# GateDriver.net
KiCad netlist of a schematic drawn in Altium Designer
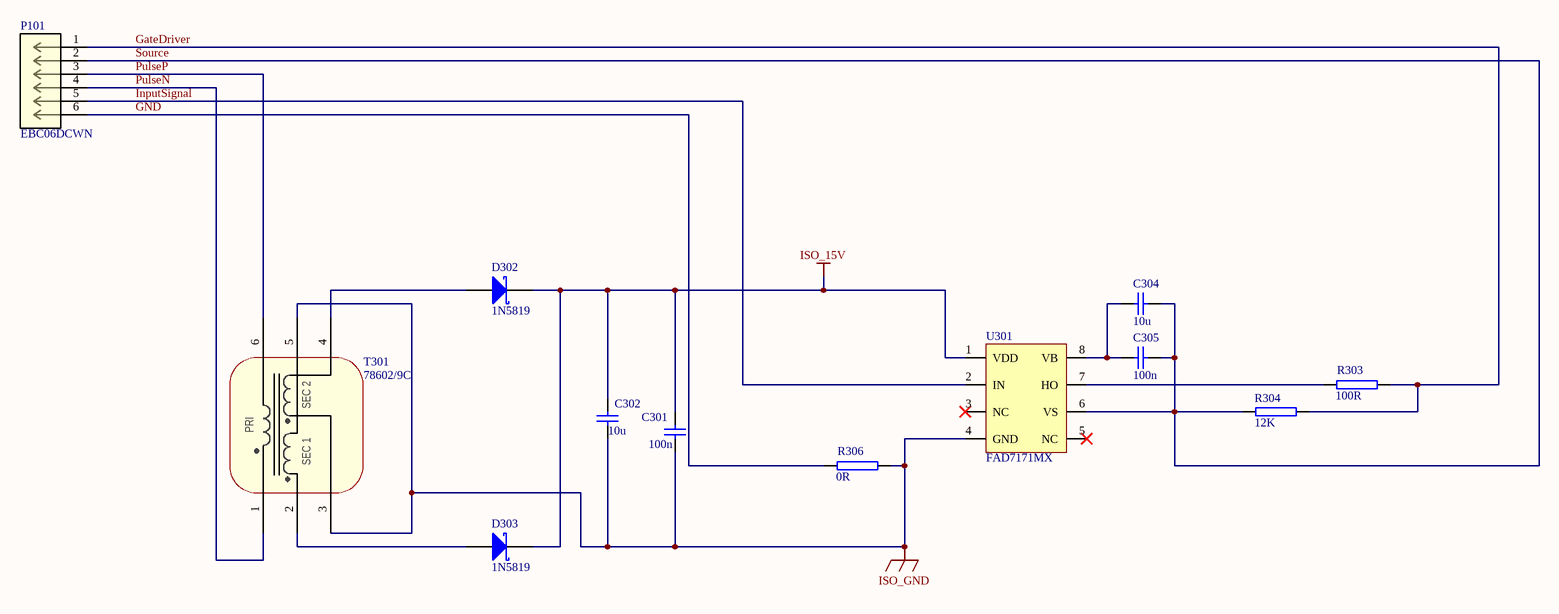
[diagram p0: GateDriver.SchDoc]

(export (version "E")
  (design (tool "Eeschema 10.0.6"))
  (components
    (comp (ref "C301")
      (value "100n")
      (footprint "CAP_1206")
      (description "Non Polarized Capacitor, SMD, 1206")
      (libsource (lib "Resistors and Capacitors") (part "CAPN 1206"))
    )
    (comp (ref "C302")
      (value "10u")
      (footprint "CAP_1206")
      (description "Non Polarized Capacitor, SMD, 1206")
      (libsource (lib "Resistors and Capacitors") (part "CAPN 1206"))
    )
    (comp (ref "C304")
      (value "10u")
      (footprint "CAP_1206")
      (description "Non Polarized Capacitor, SMD, 1206")
      (libsource (lib "Resistors and Capacitors") (part "CAPN 1206"))
    )
    (comp (ref "C305")
      (value "100n")
      (footprint "CAP_1206")
      (description "Non Polarized Capacitor, SMD, 1206")
      (libsource (lib "Resistors and Capacitors") (part "CAPN 1206"))
    )
    (comp (ref "D302")
      (value "1N5819")
      (footprint "DIODE0.4_AUT")
      (description "Schottky Diode, 1A,40v")
      (libsource (lib "Diodes") (part "1N5819"))
    )
    (comp (ref "D303")
      (value "1N5819")
      (footprint "DIODE0.4_AUT")
      (description "Schottky Diode, 1A,40v")
      (libsource (lib "Diodes") (part "1N5819"))
    )
    (comp (ref "P101")
      (value "EBC06DCWN")
      (footprint "6 Pose edge Connector")
      (description "6 Position male Connector Non Specified - Dual Edge Gold 0.100\" (2.54mm) Blue")
      (libsource (lib "ENEL709_Schematic_Library") (part "EdgeConnector"))
    )
    (comp (ref "R303")
      (value "100R")
      (footprint "RES_1206")
      (description "Resistor, SMD, 1206")
      (libsource (lib "Resistors and Capacitors") (part "Resistor 1206"))
    )
    (comp (ref "R304")
      (value "12K")
      (footprint "RES_1206")
      (description "Resistor, SMD, 1206")
      (libsource (lib "Resistors and Capacitors") (part "Resistor 1206"))
    )
    (comp (ref "R306")
      (value "0R")
      (footprint "RES_1206")
      (description "Resistor, SMD, 1206")
      (libsource (lib "Resistors and Capacitors") (part "Resistor 1206"))
    )
    (comp (ref "T301")
      (value "78602/9C")
      (footprint "DIP6W_AUT")
      (description "Pulse transformer 1:1:1")
      (libsource (lib "Projects_2025") (part "78602/9C"))
    )
    (comp (ref "U301")
      (value "FAD7171MX")
      (footprint "SOIC8-M")
      (libsource (lib "Schlib") (part "FAD7171MX"))
    )
  )
  (nets
    (net (code "1") (name "/GND") (class "Default")
      (node (ref "P101") (pin "6") (pinfunction "6_6") (pintype "passive"))
      (node (ref "R306") (pin "2") (pinfunction "2_2") (pintype "passive"))
    )
    (net (code "2") (name "/GateDriver") (class "Default")
      (node (ref "P101") (pin "1") (pinfunction "1_1") (pintype "passive"))
      (node (ref "R303") (pin "2") (pinfunction "2_2") (pintype "passive"))
      (node (ref "R304") (pin "1") (pinfunction "1_1") (pintype "passive"))
    )
    (net (code "3") (name "/InputSignal") (class "Default")
      (node (ref "P101") (pin "5") (pinfunction "5_5") (pintype "passive"))
      (node (ref "U301") (pin "2") (pinfunction "IN_2") (pintype "passive"))
    )
    (net (code "4") (name "/PulseN") (class "Default")
      (node (ref "P101") (pin "4") (pinfunction "4_4") (pintype "passive"))
      (node (ref "T301") (pin "1") (pinfunction "Pri_1_1") (pintype "power_in"))
    )
    (net (code "5") (name "/PulseP") (class "Default")
      (node (ref "P101") (pin "3") (pinfunction "3_3") (pintype "passive"))
      (node (ref "T301") (pin "6") (pinfunction "Pri2_6") (pintype "power_in"))
    )
    (net (code "6") (name "/Source") (class "Default")
      (node (ref "C304") (pin "1") (pinfunction "1_1") (pintype "passive"))
      (node (ref "C305") (pin "1") (pinfunction "1_1") (pintype "passive"))
      (node (ref "P101") (pin "2") (pinfunction "2_2") (pintype "passive"))
      (node (ref "R304") (pin "2") (pinfunction "2_2") (pintype "passive"))
      (node (ref "U301") (pin "6") (pinfunction "VS_6") (pintype "passive"))
    )
    (net (code "7") (name "ISO_15V") (class "Default")
      (node (ref "C301") (pin "2") (pinfunction "2_2") (pintype "passive"))
      (node (ref "C302") (pin "2") (pinfunction "2_2") (pintype "passive"))
      (node (ref "D302") (pin "K") (pinfunction "K_K") (pintype "passive"))
      (node (ref "D303") (pin "K") (pinfunction "K_K") (pintype "passive"))
      (node (ref "U301") (pin "1") (pinfunction "VDD_1") (pintype "passive"))
    )
    (net (code "8") (name "ISO_GND") (class "Default")
      (node (ref "C301") (pin "1") (pinfunction "1_1") (pintype "passive"))
      (node (ref "C302") (pin "1") (pinfunction "1_1") (pintype "passive"))
      (node (ref "R306") (pin "1") (pinfunction "1_1") (pintype "passive"))
      (node (ref "T301") (pin "3") (pinfunction "Sec1_2_3") (pintype "power_in"))
      (node (ref "T301") (pin "5") (pinfunction "Sec1_2_5") (pintype "power_in"))
      (node (ref "U301") (pin "4") (pinfunction "GND_4") (pintype "passive"))
    )
    (net (code "9") (name "Net-(T301-Sec1_1)") (class "Default")
      (node (ref "D303") (pin "A") (pinfunction "A_A") (pintype "passive"))
      (node (ref "T301") (pin "2") (pinfunction "Sec1_1_2") (pintype "power_in"))
    )
    (net (code "10") (name "Net-(T301-Sec2_2)") (class "Default")
      (node (ref "D302") (pin "A") (pinfunction "A_A") (pintype "passive"))
      (node (ref "T301") (pin "4") (pinfunction "Sec2_2_4") (pintype "power_in"))
    )
    (net (code "11") (name "Net-(U301-HO)") (class "Default")
      (node (ref "R303") (pin "1") (pinfunction "1_1") (pintype "passive"))
      (node (ref "U301") (pin "7") (pinfunction "HO_7") (pintype "passive"))
    )
    (net (code "12") (name "Net-(U301-VB)") (class "Default")
      (node (ref "C304") (pin "2") (pinfunction "2_2") (pintype "passive"))
      (node (ref "C305") (pin "2") (pinfunction "2_2") (pintype "passive"))
      (node (ref "U301") (pin "8") (pinfunction "VB_8") (pintype "passive"))
    )
    (net (code "13") (name "unconnected-(U301-NC-Pad3)") (class "Default")
      (node (ref "U301") (pin "3") (pinfunction "NC_3") (pintype "passive+no_connect"))
    )
    (net (code "14") (name "unconnected-(U301-NC-Pad5)") (class "Default")
      (node (ref "U301") (pin "5") (pinfunction "NC_5") (pintype "passive+no_connect"))
    )
  )
)
